# OSSC_HDMI_Audio_v1_5_A3b.net
KiCad netlist of a schematic drawn in EAGLE
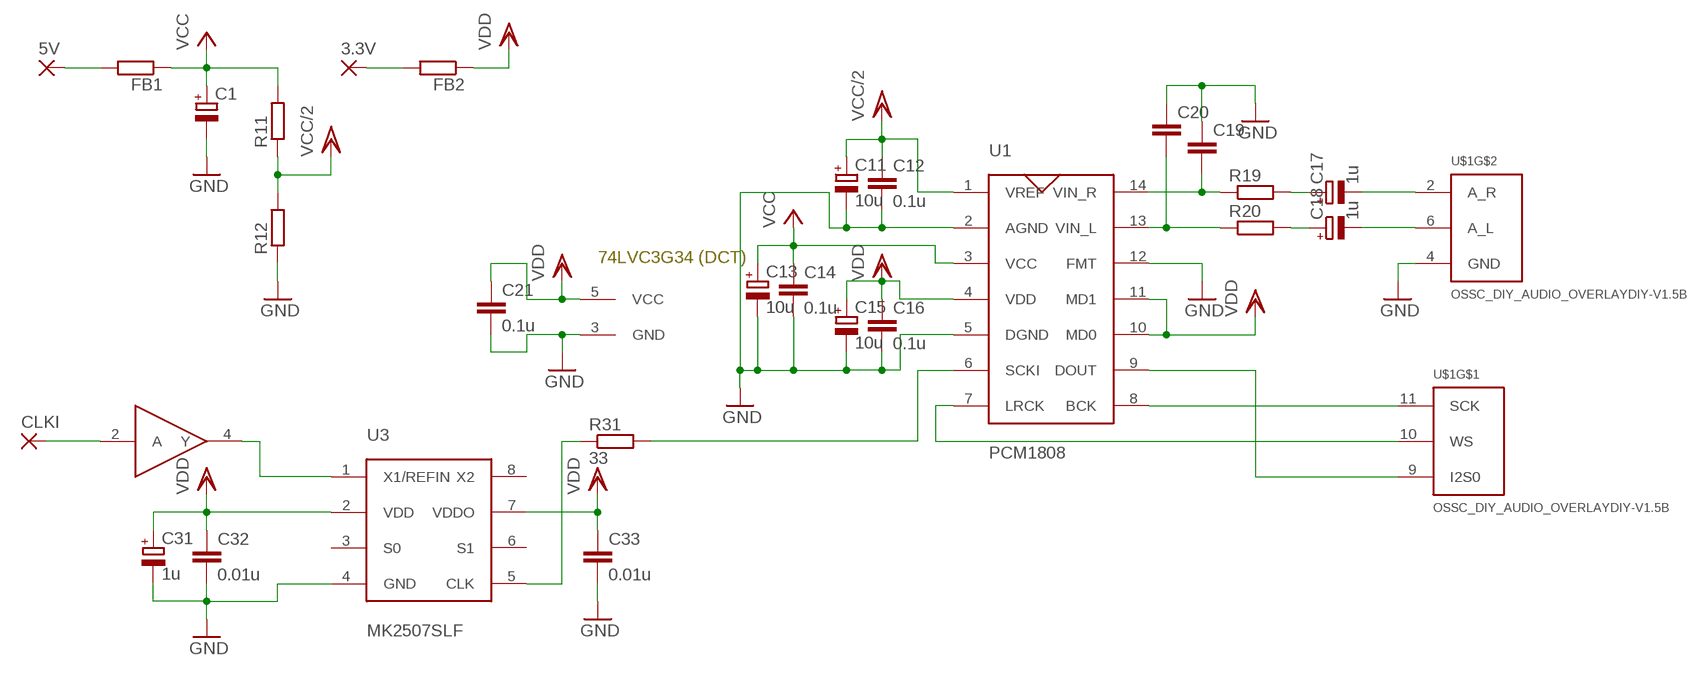
[diagram p0: schematic, sheet 1]

(export (version "E")
  (design (tool "Eeschema 10.0.6"))
  (components
    (comp (ref "3.3V")
      (value "SMD2")
      (footprint "eagle-import:SMD1,27-2,54")
      (libsource (lib "eagle-import") (part "SMD2"))
    )
    (comp (ref "5V")
      (value "SMD2")
      (footprint "eagle-import:SMD1,27-2,54")
      (libsource (lib "eagle-import") (part "SMD2"))
    )
    (comp (ref "C1")
      (value "CPOL-EUSMCC")
      (footprint "eagle-import:SMC_C")
      (libsource (lib "eagle-import") (part "CPOL-EUSMCC"))
    )
    (comp (ref "C11")
      (value "10u")
      (footprint "eagle-import:SMC_A")
      (libsource (lib "eagle-import") (part "CPOL-EUSMCA"))
    )
    (comp (ref "C12")
      (value "0.1u")
      (footprint "eagle-import:C0603")
      (libsource (lib "eagle-import") (part "C-EUC0603"))
    )
    (comp (ref "C13")
      (value "10u")
      (footprint "eagle-import:SMC_A")
      (libsource (lib "eagle-import") (part "CPOL-EUSMCA"))
    )
    (comp (ref "C14")
      (value "0.1u")
      (footprint "eagle-import:C0603")
      (libsource (lib "eagle-import") (part "C-EUC0603"))
    )
    (comp (ref "C15")
      (value "10u")
      (footprint "eagle-import:SMC_A")
      (libsource (lib "eagle-import") (part "CPOL-EUSMCA"))
    )
    (comp (ref "C16")
      (value "0.1u")
      (footprint "eagle-import:C0603")
      (libsource (lib "eagle-import") (part "C-EUC0603"))
    )
    (comp (ref "C17")
      (value "1u")
      (footprint "eagle-import:SMC_A")
      (libsource (lib "eagle-import") (part "CPOL-EUSMCA"))
    )
    (comp (ref "C18")
      (value "1u")
      (footprint "eagle-import:SMC_A")
      (libsource (lib "eagle-import") (part "CPOL-EUSMCA"))
    )
    (comp (ref "C19")
      (value "C-EUC0603")
      (footprint "eagle-import:C0603")
      (libsource (lib "eagle-import") (part "C-EUC0603"))
    )
    (comp (ref "C20")
      (value "C-EUC0603")
      (footprint "eagle-import:C0603")
      (libsource (lib "eagle-import") (part "C-EUC0603"))
    )
    (comp (ref "C21")
      (value "0.1u")
      (footprint "eagle-import:C0603")
      (libsource (lib "eagle-import") (part "C-EUC0603"))
    )
    (comp (ref "C31")
      (value "1u")
      (footprint "eagle-import:SMC_A")
      (libsource (lib "eagle-import") (part "CPOL-EUSMCA"))
    )
    (comp (ref "C32")
      (value "0.01u")
      (footprint "eagle-import:C0603")
      (libsource (lib "eagle-import") (part "C-EUC0603"))
    )
    (comp (ref "C33")
      (value "0.01u")
      (footprint "eagle-import:C0603")
      (libsource (lib "eagle-import") (part "C-EUC0603"))
    )
    (comp (ref "CLKI")
      (value "SMD2")
      (footprint "eagle-import:SMD1,27-2,54")
      (libsource (lib "eagle-import") (part "SMD2"))
    )
    (comp (ref "FB1")
      (value "R-EU_R0603")
      (footprint "eagle-import:R0603")
      (libsource (lib "eagle-import") (part "R-EU_R0603"))
    )
    (comp (ref "FB2")
      (value "R-EU_R0603")
      (footprint "eagle-import:R0603")
      (libsource (lib "eagle-import") (part "R-EU_R0603"))
    )
    (comp (ref "R11")
      (value "R-EU_R0603")
      (footprint "eagle-import:R0603")
      (libsource (lib "eagle-import") (part "R-EU_R0603"))
    )
    (comp (ref "R12")
      (value "R-EU_R0603")
      (footprint "eagle-import:R0603")
      (libsource (lib "eagle-import") (part "R-EU_R0603"))
    )
    (comp (ref "R19")
      (value "R-EU_R0603")
      (footprint "eagle-import:R0603")
      (libsource (lib "eagle-import") (part "R-EU_R0603"))
    )
    (comp (ref "R20")
      (value "R-EU_R0603")
      (footprint "eagle-import:R0603")
      (libsource (lib "eagle-import") (part "R-EU_R0603"))
    )
    (comp (ref "R31")
      (value "33")
      (footprint "eagle-import:R0603")
      (libsource (lib "eagle-import") (part "R-EU_R0603"))
    )
    (comp (ref "U$1")
      (value "OSSC_DIY_AUDIO_OVERLAYDIY-V1.5B")
      (footprint "eagle-import:OSSC_OVERLAY_V1.5B")
      (libsource (lib "eagle-import") (part "OSSC_DIY_AUDIO_OVERLAYDIY-V1.5B"))
    )
    (comp (ref "U1")
      (value "PCM1808")
      (footprint "eagle-import:PCM1808")
      (libsource (lib "eagle-import") (part "PCM1808"))
    )
    (comp (ref "U2")
      (value "74LVC1G34")
      (footprint "eagle-import:74LVC1G34DCK")
      (libsource (lib "eagle-import") (part "74LVC1G34"))
    )
    (comp (ref "U3")
      (value "MK2507SLF")
      (footprint "eagle-import:SOIC8")
      (libsource (lib "eagle-import") (part "MK2507SLF"))
    )
  )
  (nets
    (net (code "1") (name "GND") (class "Default")
      (node (ref "C1") (pin "-") (pinfunction "-_-") (pintype "passive"))
      (node (ref "C11") (pin "-") (pinfunction "-_-") (pintype "passive"))
      (node (ref "C12") (pin "2") (pinfunction "2_2") (pintype "passive"))
      (node (ref "C13") (pin "-") (pinfunction "-_-") (pintype "passive"))
      (node (ref "C14") (pin "2") (pinfunction "2_2") (pintype "passive"))
      (node (ref "C15") (pin "-") (pinfunction "-_-") (pintype "passive"))
      (node (ref "C16") (pin "2") (pinfunction "2_2") (pintype "passive"))
      (node (ref "C19") (pin "1") (pinfunction "1_1") (pintype "passive"))
      (node (ref "C20") (pin "1") (pinfunction "1_1") (pintype "passive"))
      (node (ref "C21") (pin "2") (pinfunction "2_2") (pintype "passive"))
      (node (ref "C31") (pin "-") (pinfunction "-_-") (pintype "passive"))
      (node (ref "C32") (pin "2") (pinfunction "2_2") (pintype "passive"))
      (node (ref "C33") (pin "2") (pinfunction "2_2") (pintype "passive"))
      (node (ref "R12") (pin "1") (pinfunction "1_1") (pintype "passive"))
      (node (ref "U$1") (pin "4") (pinfunction "GND_4") (pintype "bidirectional"))
      (node (ref "U1") (pin "12") (pinfunction "FMT_12") (pintype "bidirectional"))
      (node (ref "U1") (pin "2") (pinfunction "AGND_2") (pintype "bidirectional"))
      (node (ref "U1") (pin "5") (pinfunction "DGND_5") (pintype "bidirectional"))
      (node (ref "U2") (pin "3") (pinfunction "GND_3") (pintype "bidirectional"))
      (node (ref "U3") (pin "4") (pinfunction "GND_4") (pintype "bidirectional"))
    )
    (net (code "2") (name "Net-(3.3V-P)") (class "Default")
      (node (ref "3.3V") (pin "1") (pinfunction "P_1") (pintype "passive"))
      (node (ref "FB2") (pin "2") (pinfunction "2_2") (pintype "passive"))
    )
    (net (code "3") (name "Net-(5V-P)") (class "Default")
      (node (ref "5V") (pin "1") (pinfunction "P_1") (pintype "passive"))
      (node (ref "FB1") (pin "2") (pinfunction "2_2") (pintype "passive"))
    )
    (net (code "4") (name "Net-(C17-Pad+)") (class "Default")
      (node (ref "C17") (pin "+") (pinfunction "+_+") (pintype "passive"))
      (node (ref "R19") (pin "2") (pinfunction "2_2") (pintype "passive"))
    )
    (net (code "5") (name "Net-(C18-Pad+)") (class "Default")
      (node (ref "C18") (pin "+") (pinfunction "+_+") (pintype "passive"))
      (node (ref "R20") (pin "2") (pinfunction "2_2") (pintype "passive"))
    )
    (net (code "6") (name "Net-(CLKI-P)") (class "Default")
      (node (ref "CLKI") (pin "1") (pinfunction "P_1") (pintype "passive"))
      (node (ref "U2") (pin "2") (pinfunction "A_2") (pintype "bidirectional"))
    )
    (net (code "7") (name "Net-(U$1A-I2S0)") (class "Default")
      (node (ref "U$1") (pin "9") (pinfunction "I2S0_9") (pintype "bidirectional"))
      (node (ref "U1") (pin "9") (pinfunction "DOUT_9") (pintype "bidirectional"))
    )
    (net (code "8") (name "Net-(U$1A-SCK)") (class "Default")
      (node (ref "U$1") (pin "11") (pinfunction "SCK_11") (pintype "bidirectional"))
      (node (ref "U1") (pin "8") (pinfunction "BCK_8") (pintype "bidirectional"))
    )
    (net (code "9") (name "Net-(U$1A-WS)") (class "Default")
      (node (ref "U$1") (pin "10") (pinfunction "WS_10") (pintype "bidirectional"))
      (node (ref "U1") (pin "7") (pinfunction "LRCK_7") (pintype "bidirectional"))
    )
    (net (code "10") (name "Net-(U$1B-A_L)") (class "Default")
      (node (ref "C18") (pin "-") (pinfunction "-_-") (pintype "passive"))
      (node (ref "U$1") (pin "6") (pinfunction "A_L_6") (pintype "bidirectional"))
    )
    (net (code "11") (name "Net-(U$1B-A_R)") (class "Default")
      (node (ref "C17") (pin "-") (pinfunction "-_-") (pintype "passive"))
      (node (ref "U$1") (pin "2") (pinfunction "A_R_2") (pintype "bidirectional"))
    )
    (net (code "12") (name "Net-(U1-SCKI)") (class "Default")
      (node (ref "R31") (pin "2") (pinfunction "2_2") (pintype "passive"))
      (node (ref "U1") (pin "6") (pinfunction "SCKI_6") (pintype "bidirectional"))
    )
    (net (code "13") (name "Net-(U1-VIN_L)") (class "Default")
      (node (ref "C20") (pin "2") (pinfunction "2_2") (pintype "passive"))
      (node (ref "R20") (pin "1") (pinfunction "1_1") (pintype "passive"))
      (node (ref "U1") (pin "13") (pinfunction "VIN_L_13") (pintype "bidirectional"))
    )
    (net (code "14") (name "Net-(U1-VIN_R)") (class "Default")
      (node (ref "C19") (pin "2") (pinfunction "2_2") (pintype "passive"))
      (node (ref "R19") (pin "1") (pinfunction "1_1") (pintype "passive"))
      (node (ref "U1") (pin "14") (pinfunction "VIN_R_14") (pintype "bidirectional"))
    )
    (net (code "15") (name "Net-(U2A-Y)") (class "Default")
      (node (ref "U2") (pin "4") (pinfunction "Y_4") (pintype "bidirectional"))
      (node (ref "U3") (pin "1") (pinfunction "X1/REFIN_1") (pintype "bidirectional"))
    )
    (net (code "16") (name "Net-(U3-CLK)") (class "Default")
      (node (ref "R31") (pin "1") (pinfunction "1_1") (pintype "passive"))
      (node (ref "U3") (pin "5") (pinfunction "CLK_5") (pintype "bidirectional"))
    )
    (net (code "17") (name "VCC") (class "Default")
      (node (ref "C1") (pin "+") (pinfunction "+_+") (pintype "passive"))
      (node (ref "C13") (pin "+") (pinfunction "+_+") (pintype "passive"))
      (node (ref "C14") (pin "1") (pinfunction "1_1") (pintype "passive"))
      (node (ref "FB1") (pin "1") (pinfunction "1_1") (pintype "passive"))
      (node (ref "R11") (pin "2") (pinfunction "2_2") (pintype "passive"))
      (node (ref "U1") (pin "3") (pinfunction "VCC_3") (pintype "bidirectional"))
    )
    (net (code "18") (name "VCC{slash}2") (class "Default")
      (node (ref "C11") (pin "+") (pinfunction "+_+") (pintype "passive"))
      (node (ref "C12") (pin "1") (pinfunction "1_1") (pintype "passive"))
      (node (ref "R11") (pin "1") (pinfunction "1_1") (pintype "passive"))
      (node (ref "R12") (pin "2") (pinfunction "2_2") (pintype "passive"))
      (node (ref "U1") (pin "1") (pinfunction "VREF_1") (pintype "bidirectional"))
    )
    (net (code "19") (name "VDD") (class "Default")
      (node (ref "C15") (pin "+") (pinfunction "+_+") (pintype "passive"))
      (node (ref "C16") (pin "1") (pinfunction "1_1") (pintype "passive"))
      (node (ref "C21") (pin "1") (pinfunction "1_1") (pintype "passive"))
      (node (ref "C31") (pin "+") (pinfunction "+_+") (pintype "passive"))
      (node (ref "C32") (pin "1") (pinfunction "1_1") (pintype "passive"))
      (node (ref "C33") (pin "1") (pinfunction "1_1") (pintype "passive"))
      (node (ref "FB2") (pin "1") (pinfunction "1_1") (pintype "passive"))
      (node (ref "U1") (pin "10") (pinfunction "MD0_10") (pintype "bidirectional"))
      (node (ref "U1") (pin "11") (pinfunction "MD1_11") (pintype "bidirectional"))
      (node (ref "U1") (pin "4") (pinfunction "VDD_4") (pintype "bidirectional"))
      (node (ref "U2") (pin "5") (pinfunction "VCC_5") (pintype "bidirectional"))
      (node (ref "U3") (pin "2") (pinfunction "VDD_2") (pintype "bidirectional"))
      (node (ref "U3") (pin "7") (pinfunction "VDDO_7") (pintype "bidirectional"))
    )
    (net (code "20") (name "unconnected-(U3-S0-Pad3)") (class "Default")
      (node (ref "U3") (pin "3") (pinfunction "S0_3") (pintype "bidirectional"))
    )
    (net (code "21") (name "unconnected-(U3-S1-Pad6)") (class "Default")
      (node (ref "U3") (pin "6") (pinfunction "S1_6") (pintype "bidirectional"))
    )
    (net (code "22") (name "unconnected-(U3-X2-Pad8)") (class "Default")
      (node (ref "U3") (pin "8") (pinfunction "X2_8") (pintype "bidirectional"))
    )
  )
)
